# PCB_Telemetria_2020.net
KiCad netlist of a schematic drawn in EAGLE
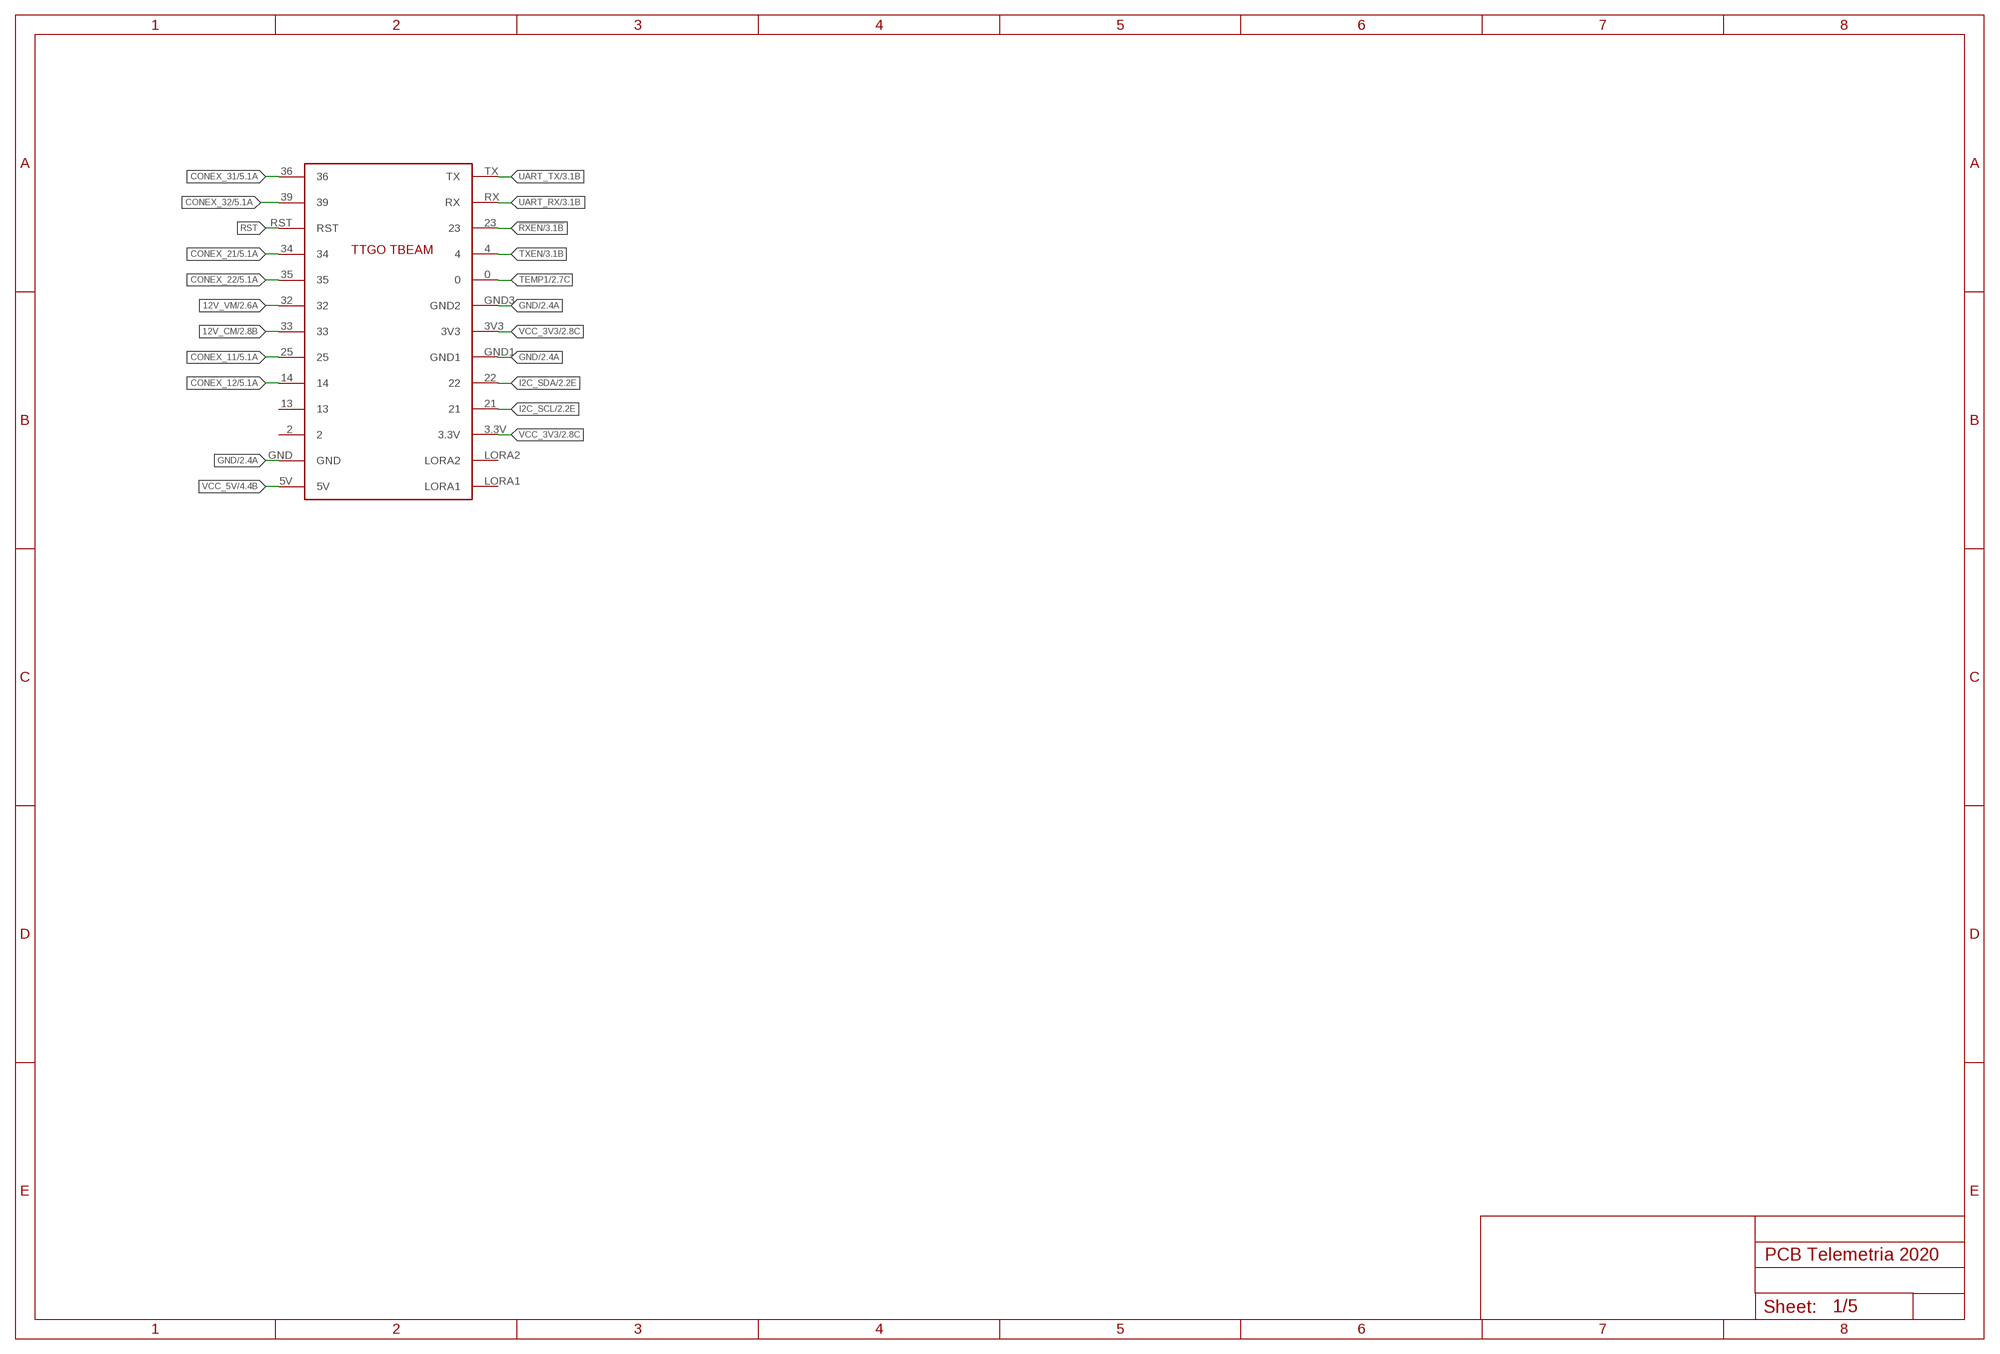
[diagram p0: schematic, sheet 1]
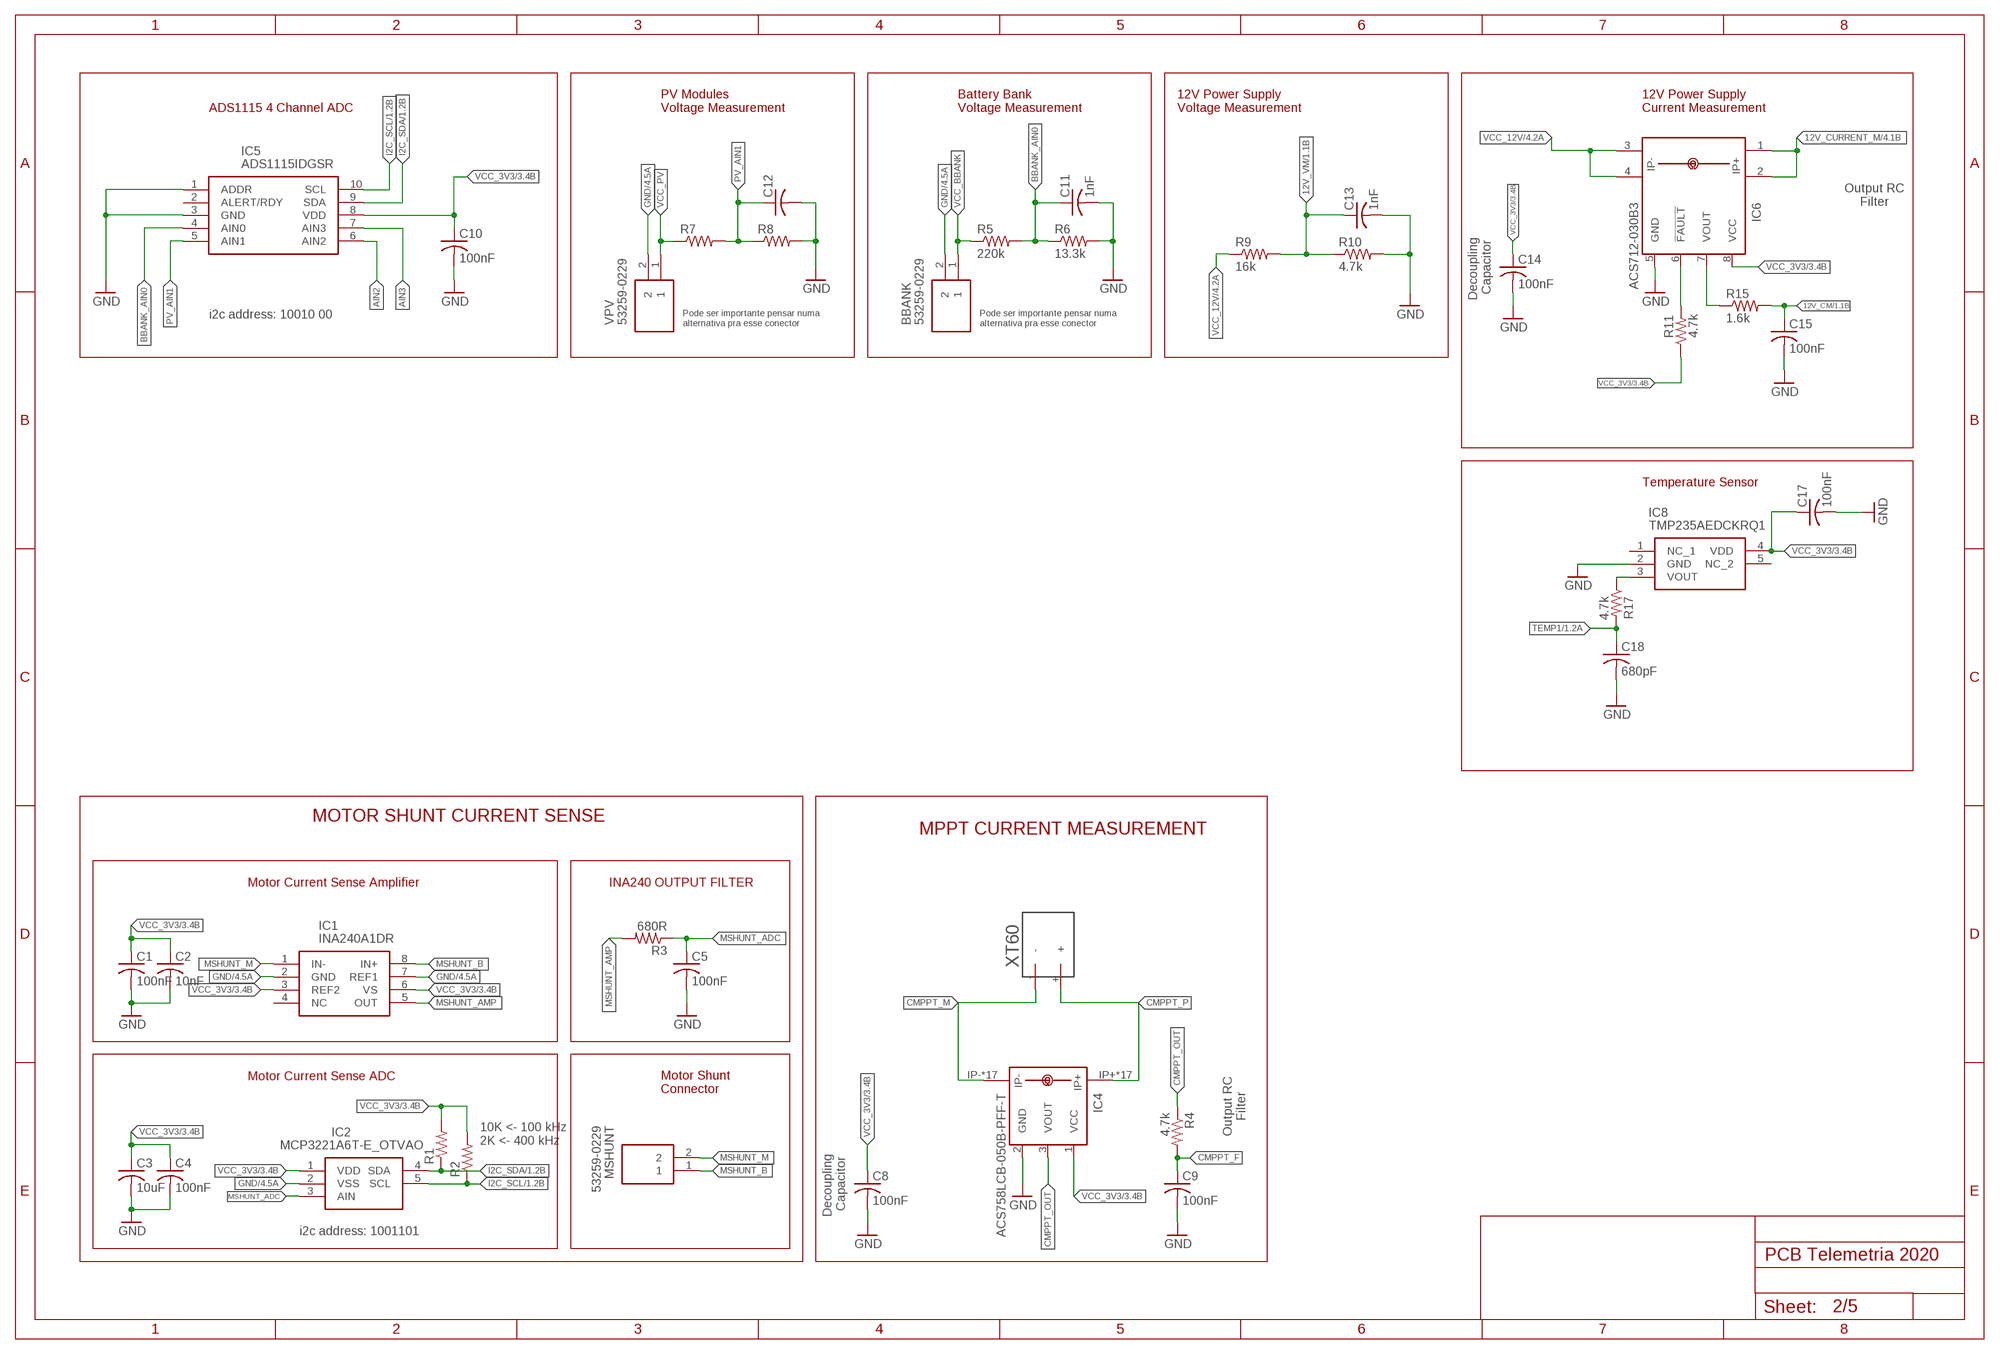
[diagram p1: schematic, sheet 2]
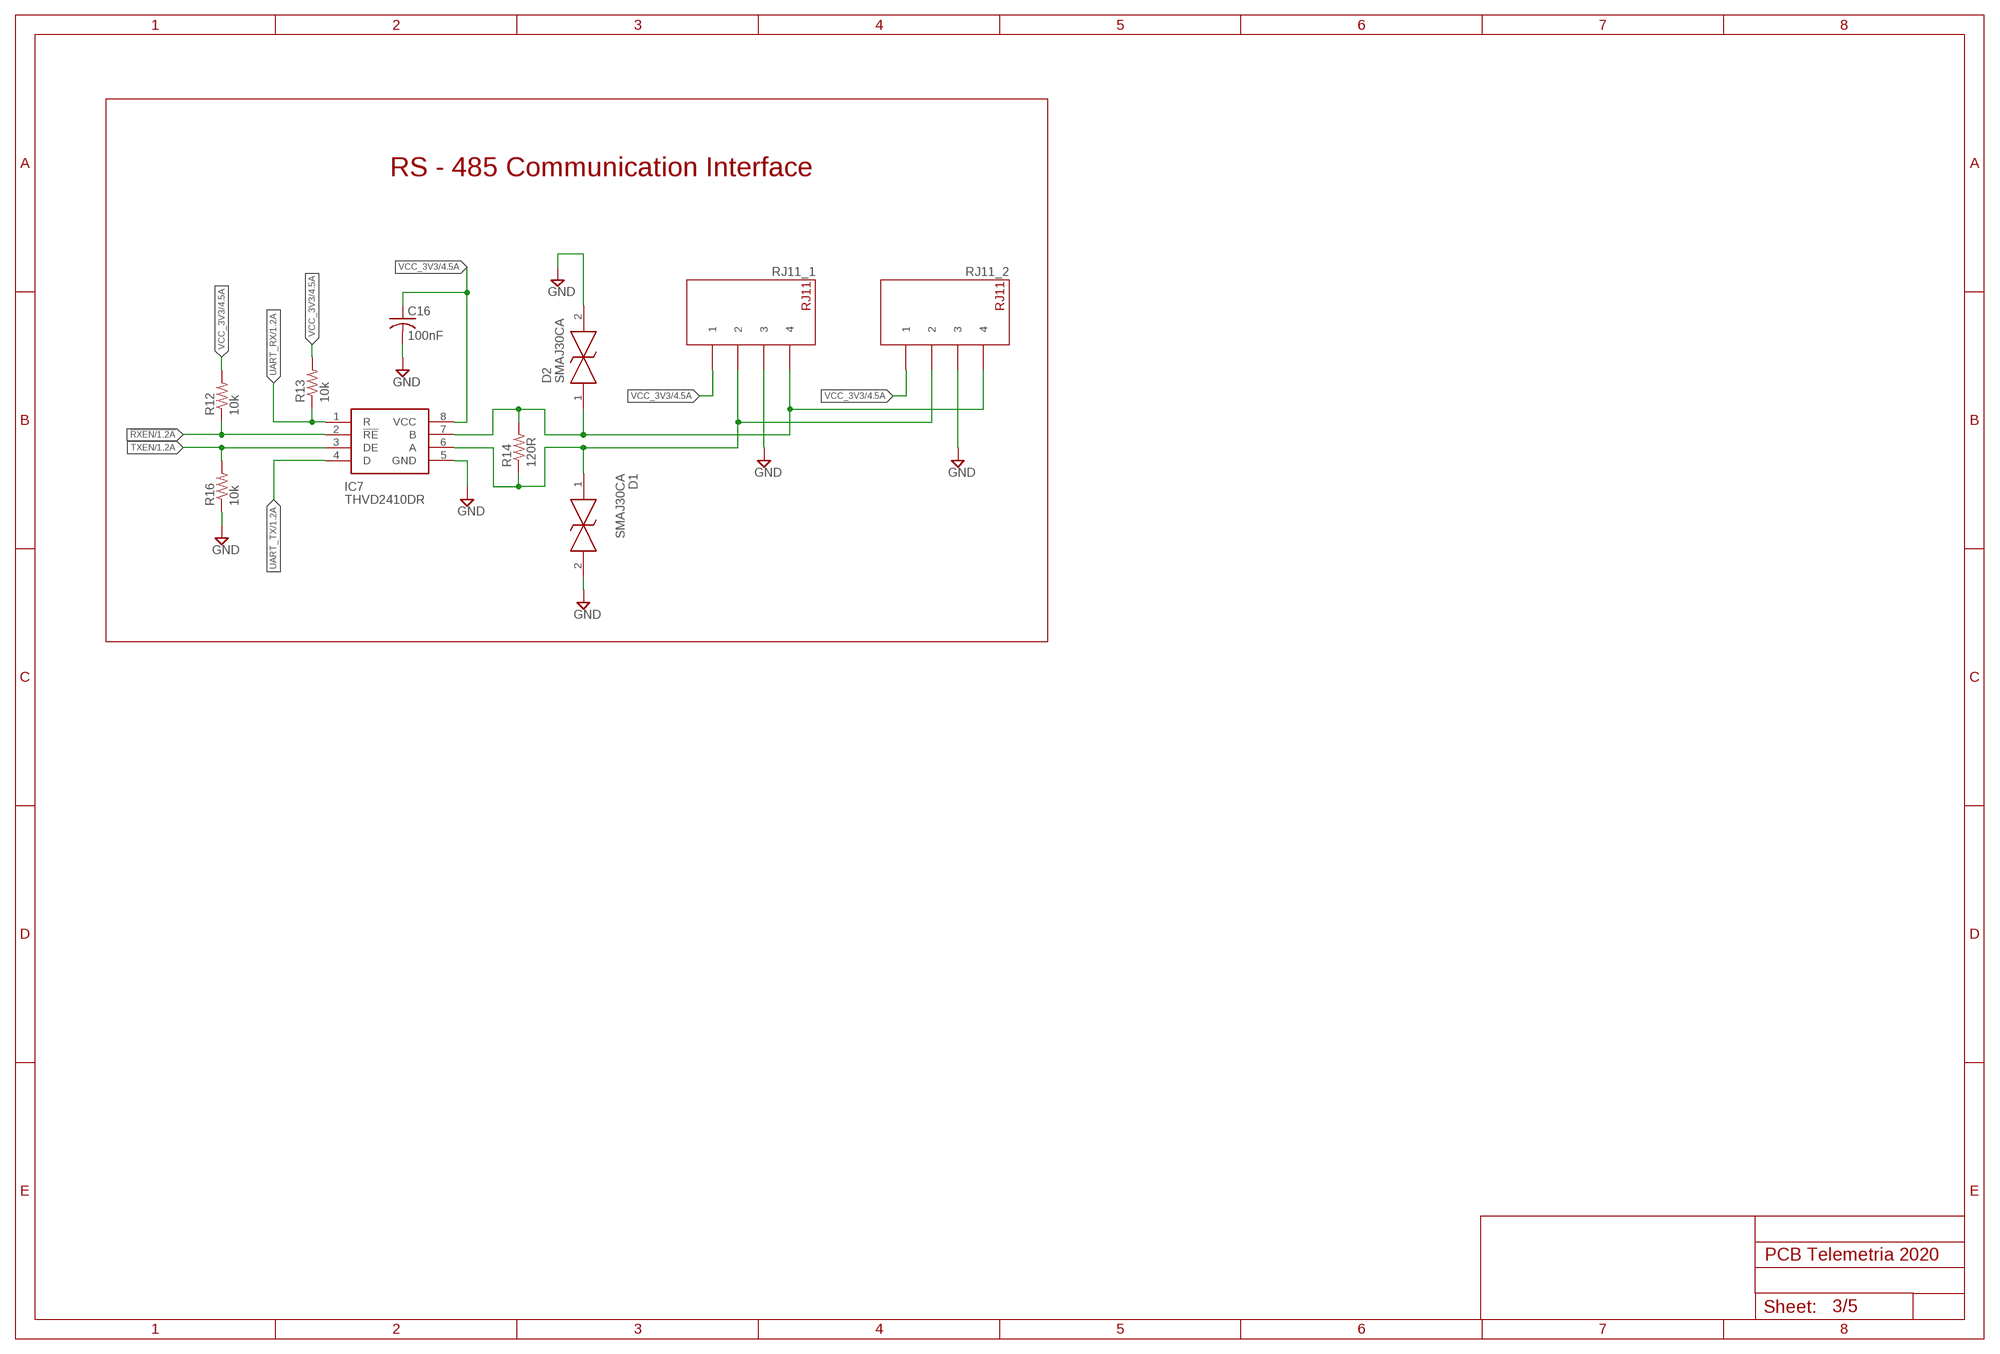
[diagram p2: schematic, sheet 3]
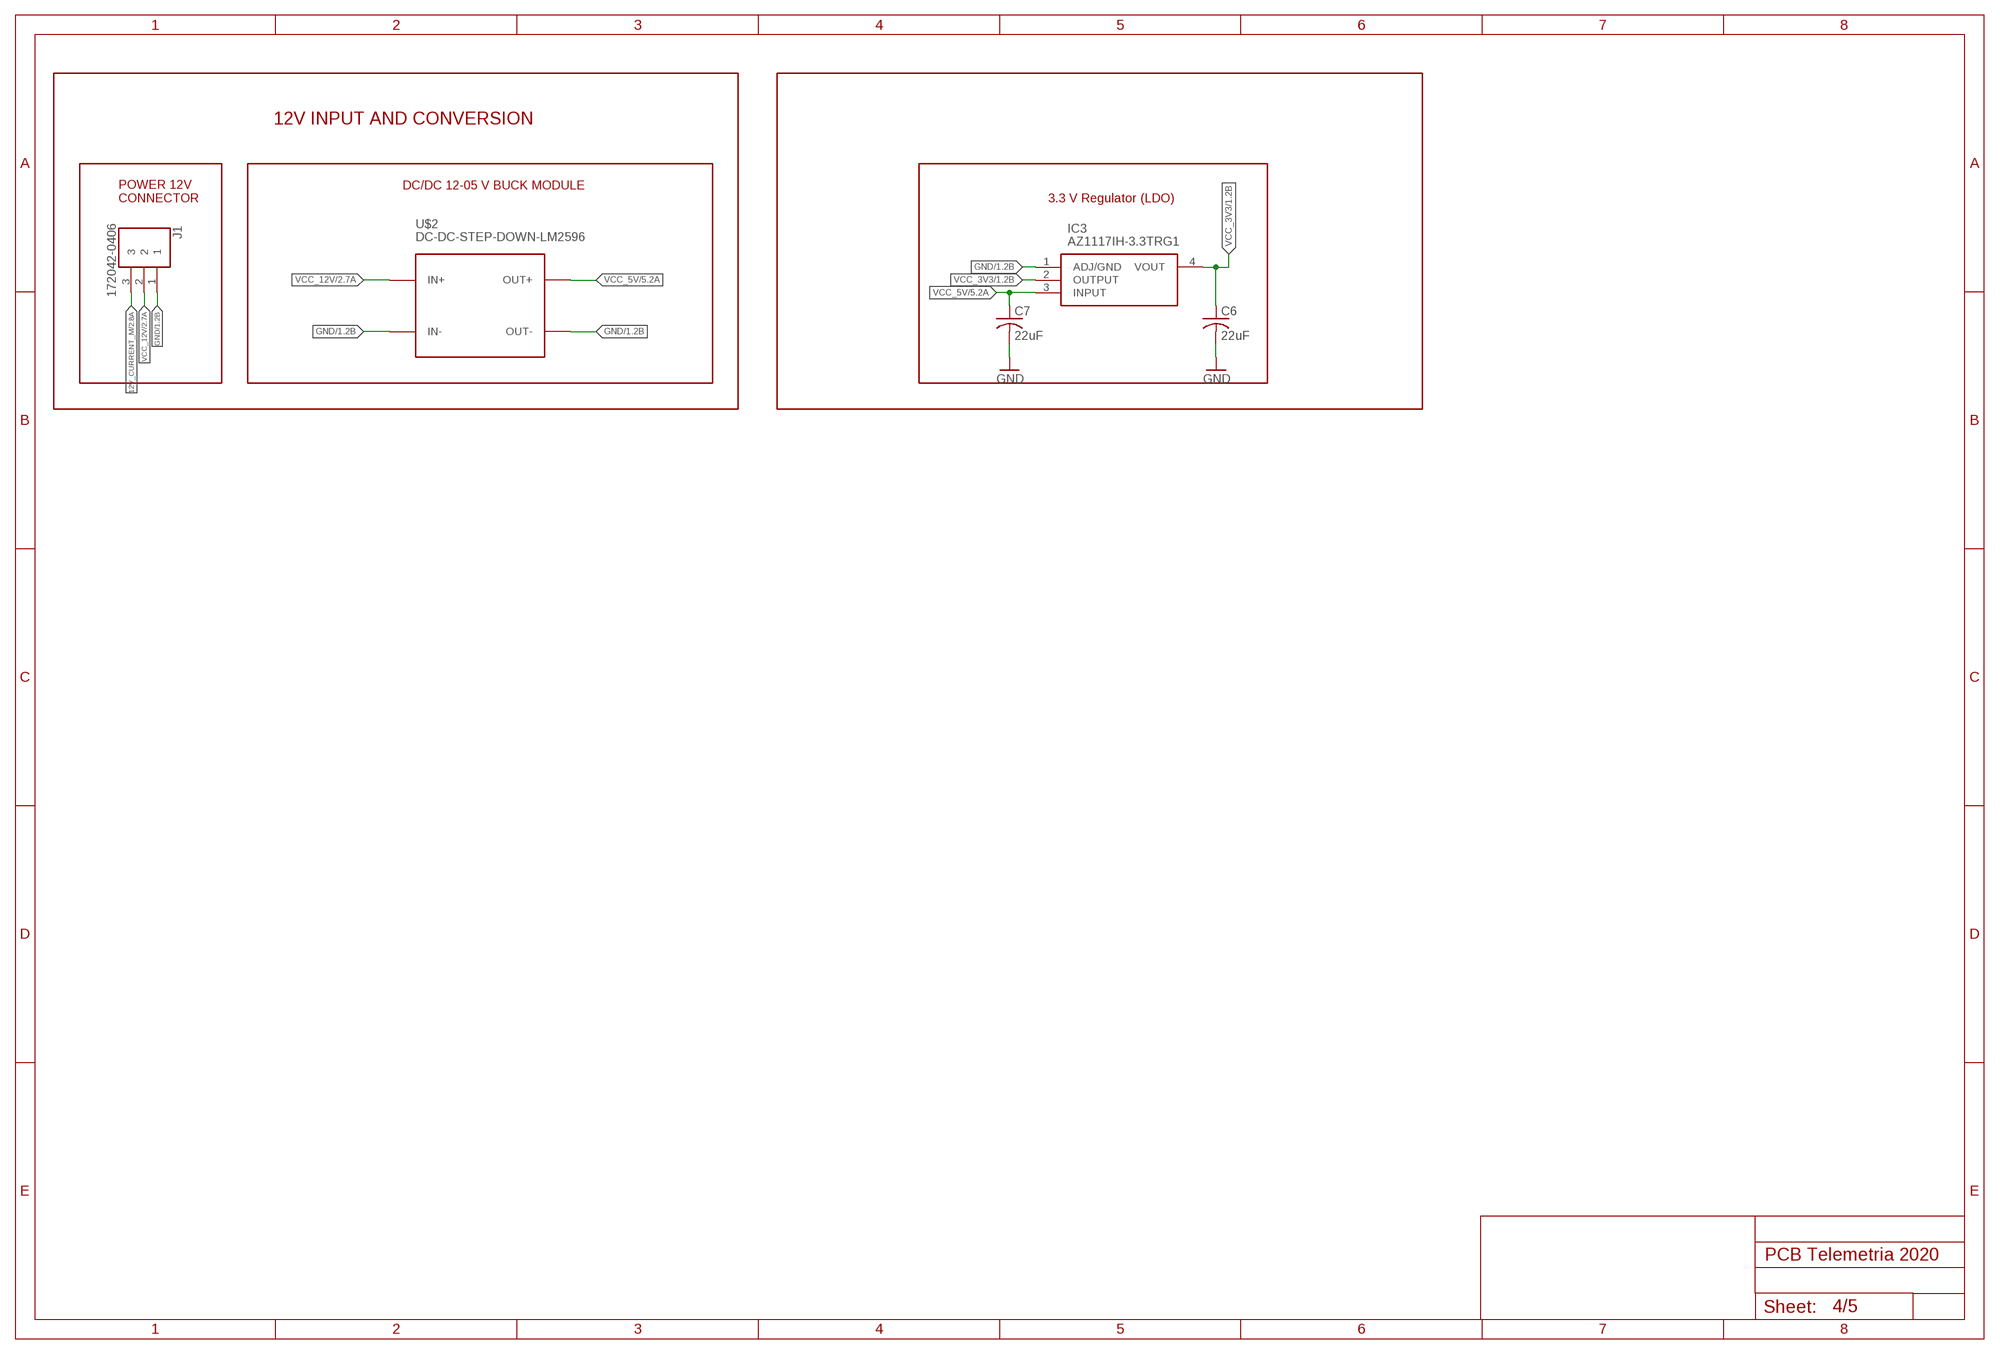
[diagram p3: schematic, sheet 4]
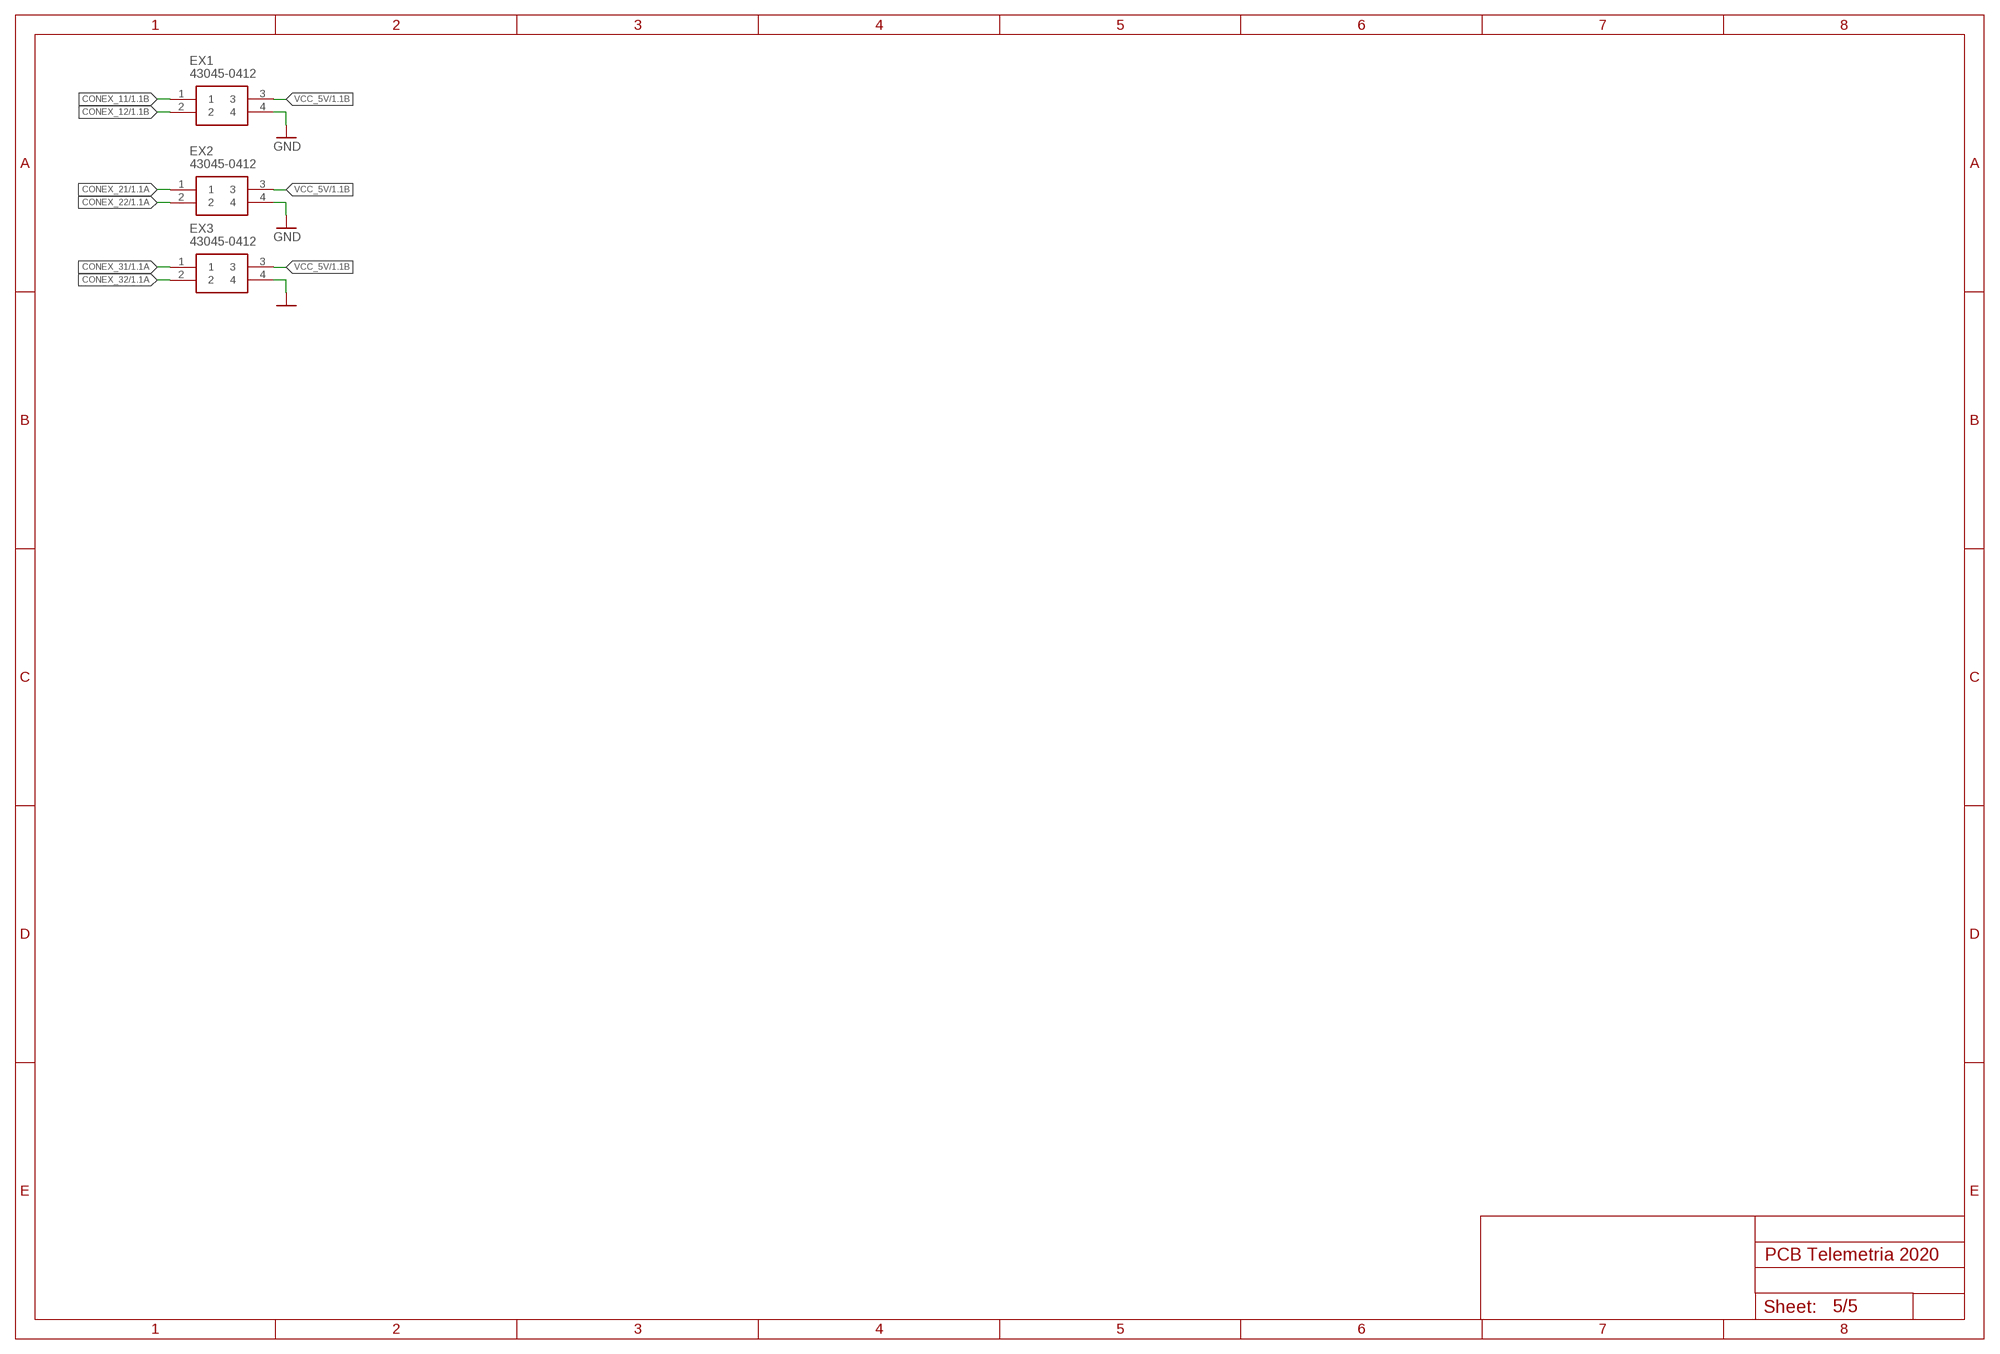
[diagram p4: schematic, sheet 5]

(export (version "E")
  (design (tool "Eeschema 10.0.6"))
  (components
    (comp (ref "U$1")
      (value "TTGOBEAM")
      (footprint "eagle-import:TTGOBEAM")
      (libsource (lib "eagle-import") (part "TTGOBEAM"))
    )
    (comp (ref "EX1")
      (value "43045-0412")
      (footprint "eagle-import:43045-0412")
      (fields (field (name "MOUSER_PART_NUMBER") "538-43045-0412"))
      (libsource (lib "eagle-import") (part "43045-0412"))
    )
    (comp (ref "EX2")
      (value "43045-0412")
      (footprint "eagle-import:43045-0412")
      (fields (field (name "MOUSER_PART_NUMBER") "538-43045-0412"))
      (libsource (lib "eagle-import") (part "43045-0412"))
    )
    (comp (ref "EX3")
      (value "43045-0412")
      (footprint "eagle-import:43045-0412")
      (fields (field (name "MOUSER_PART_NUMBER") "538-43045-0412"))
      (libsource (lib "eagle-import") (part "43045-0412"))
    )
    (comp (ref "C16")
      (value "100nF")
      (footprint "eagle-import:C0805")
      (libsource (lib "eagle-import") (part "C-USC0805"))
    )
    (comp (ref "D1")
      (value "SMAJ30CA")
      (footprint "eagle-import:DIONM5026X229N")
      (fields (field (name "MOUSER_PART_NUMBER") "576-SMAJ30CA"))
      (libsource (lib "eagle-import") (part "SMAJ30CA"))
    )
    (comp (ref "D2")
      (value "SMAJ30CA")
      (footprint "eagle-import:DIONM5026X229N")
      (fields (field (name "MOUSER_PART_NUMBER") "576-SMAJ30CA"))
      (libsource (lib "eagle-import") (part "SMAJ30CA"))
    )
    (comp (ref "IC7")
      (value "THVD2410DR")
      (footprint "eagle-import:SOIC127P600X175-8N")
      (fields (field (name "MOUSER_PART_NUMBER") "595-THVD2410DR"))
      (libsource (lib "eagle-import") (part "THVD2410DR"))
    )
    (comp (ref "R12")
      (value "10k")
      (footprint "eagle-import:M0805")
      (libsource (lib "eagle-import") (part "R-US_M0805"))
    )
    (comp (ref "R13")
      (value "10k")
      (footprint "eagle-import:M0805")
      (libsource (lib "eagle-import") (part "R-US_M0805"))
    )
    (comp (ref "R14")
      (value "120R")
      (footprint "eagle-import:M0805")
      (libsource (lib "eagle-import") (part "R-US_M0805"))
    )
    (comp (ref "R16")
      (value "10k")
      (footprint "eagle-import:M0805")
      (libsource (lib "eagle-import") (part "R-US_M0805"))
    )
    (comp (ref "RJ11_1")
      (value "TFC44")
      (footprint "eagle-import:TFC44")
      (libsource (lib "eagle-import") (part "TFC44"))
    )
    (comp (ref "RJ11_2")
      (value "TFC44")
      (footprint "eagle-import:TFC44")
      (libsource (lib "eagle-import") (part "TFC44"))
    )
    (comp (ref "C6")
      (value "22uF")
      (footprint "eagle-import:C0805")
      (libsource (lib "eagle-import") (part "C-USC0805"))
    )
    (comp (ref "C7")
      (value "22uF")
      (footprint "eagle-import:C0805")
      (libsource (lib "eagle-import") (part "C-USC0805"))
    )
    (comp (ref "IC3")
      (value "AZ1117IH-3.3TRG1")
      (footprint "eagle-import:SOT230P700X170-4N")
      (fields (field (name "MOUSER_PART_NUMBER") "621-AZ1117IH-3.3TRG1"))
      (libsource (lib "eagle-import") (part "AZ1117IH-3.3TRG1"))
    )
    (comp (ref "J1")
      (value "172042-0406")
      (footprint "eagle-import:MOLEX_172042-0406")
      (fields (field (name "MF") "Molex") (field (name "MP") "172042-0302"))
      (libsource (lib "eagle-import") (part "172042-0406"))
    )
    (comp (ref "U$2")
      (value "DC-DC-STEP-DOWN-LM2596")
      (footprint "eagle-import:DC-DC-STEP-DOWN-LM2596")
      (libsource (lib "eagle-import") (part "DC-DC-STEP-DOWN-LM2596"))
    )
    (comp (ref "BBANK")
      (value "53259-0229")
      (footprint "eagle-import:0532590229")
      (fields (field (name "MOUSER_PART_NUMBER") "538-53259-0229"))
      (libsource (lib "eagle-import") (part "53259-0229"))
    )
    (comp (ref "C1")
      (value "100nF")
      (footprint "eagle-import:C0805")
      (libsource (lib "eagle-import") (part "C-USC0805"))
    )
    (comp (ref "C2")
      (value "10nF")
      (footprint "eagle-import:C0805")
      (libsource (lib "eagle-import") (part "C-USC0805"))
    )
    (comp (ref "C3")
      (value "10uF")
      (footprint "eagle-import:C0805")
      (libsource (lib "eagle-import") (part "C-USC0805"))
    )
    (comp (ref "C4")
      (value "100nF")
      (footprint "eagle-import:C0805")
      (libsource (lib "eagle-import") (part "C-USC0805"))
    )
    (comp (ref "C5")
      (value "100nF")
      (footprint "eagle-import:C0805")
      (libsource (lib "eagle-import") (part "C-USC0805"))
    )
    (comp (ref "C8")
      (value "100nF")
      (footprint "eagle-import:C0805")
      (libsource (lib "eagle-import") (part "C-USC0805"))
    )
    (comp (ref "C9")
      (value "100nF")
      (footprint "eagle-import:C0805")
      (libsource (lib "eagle-import") (part "C-USC0805"))
    )
    (comp (ref "C10")
      (value "100nF")
      (footprint "eagle-import:C0805")
      (libsource (lib "eagle-import") (part "C-USC0805"))
    )
    (comp (ref "C11")
      (value "1nF")
      (footprint "eagle-import:C0805")
      (libsource (lib "eagle-import") (part "C-USC0805"))
    )
    (comp (ref "C12")
      (value "C-USC0805")
      (footprint "eagle-import:C0805")
      (libsource (lib "eagle-import") (part "C-USC0805"))
    )
    (comp (ref "C13")
      (value "1nF")
      (footprint "eagle-import:C0805")
      (libsource (lib "eagle-import") (part "C-USC0805"))
    )
    (comp (ref "C14")
      (value "100nF")
      (footprint "eagle-import:C0805")
      (libsource (lib "eagle-import") (part "C-USC0805"))
    )
    (comp (ref "C15")
      (value "100nF")
      (footprint "eagle-import:C0805")
      (libsource (lib "eagle-import") (part "C-USC0805"))
    )
    (comp (ref "C17")
      (value "100nF")
      (footprint "eagle-import:C0805")
      (libsource (lib "eagle-import") (part "C-USC0805"))
    )
    (comp (ref "C18")
      (value "680pF")
      (footprint "eagle-import:C0805")
      (libsource (lib "eagle-import") (part "C-USC0805"))
    )
    (comp (ref "IC1")
      (value "INA240A1DR")
      (footprint "eagle-import:SOIC127P600X175-8N")
      (fields (field (name "MOUSER_PART_NUMBER") "595-INA240A1DR"))
      (libsource (lib "eagle-import") (part "INA240A1DR"))
    )
    (comp (ref "IC2")
      (value "MCP3221A6T-E_OTVAO")
      (footprint "eagle-import:SOT95P280X145-5N")
      (fields
        (field (name "MANUFACTURER_PART_NUMBER") "MCP3221A6T-E/OTVAO")
        (field (name "MOUSER_PART_NUMBER") "579-MCP3221A6TEOTVAO")
      )
      (libsource (lib "eagle-import") (part "MCP3221A6T-E_OTVAO"))
    )
    (comp (ref "IC4")
      (value "ACS758LCB-050B-PFF-T")
      (footprint "eagle-import:CB-PFF")
      (libsource (lib "eagle-import") (part "ACS758LCB-050B-PFF-T"))
    )
    (comp (ref "IC5")
      (value "ADS1115IDGSR")
      (footprint "eagle-import:SOP50P490X110-10N")
      (fields (field (name "MOUSER_PART_NUMBER") "595-ADS1115IDGSR"))
      (libsource (lib "eagle-import") (part "ADS1115IDGSR"))
    )
    (comp (ref "IC6")
      (value "ACS712-030B3")
      (footprint "eagle-import:SOIC8")
      (libsource (lib "eagle-import") (part "ACS712-LC"))
    )
    (comp (ref "IC8")
      (value "TMP235AEDCKRQ1")
      (footprint "eagle-import:SOT65P210X110-5N")
      (fields (field (name "MOUSER_PART_NUMBER") "595-TMP235AEDCKRQ1"))
      (libsource (lib "eagle-import") (part "TMP235AEDCKRQ1"))
    )
    (comp (ref "MSHUNT")
      (value "53259-0229")
      (footprint "eagle-import:0532590229")
      (fields (field (name "MOUSER_PART_NUMBER") "538-53259-0229"))
      (libsource (lib "eagle-import") (part "53259-0229"))
    )
    (comp (ref "R1")
      (value "R-US_R0805")
      (footprint "eagle-import:R0805")
      (libsource (lib "eagle-import") (part "R-US_R0805"))
    )
    (comp (ref "R2")
      (value "R-US_R0805")
      (footprint "eagle-import:R0805")
      (libsource (lib "eagle-import") (part "R-US_R0805"))
    )
    (comp (ref "R3")
      (value "680R")
      (footprint "eagle-import:R0805")
      (libsource (lib "eagle-import") (part "R-US_R0805"))
    )
    (comp (ref "R4")
      (value "4.7k")
      (footprint "eagle-import:R0805")
      (libsource (lib "eagle-import") (part "R-US_R0805"))
    )
    (comp (ref "R5")
      (value "220k")
      (footprint "eagle-import:R0805")
      (libsource (lib "eagle-import") (part "R-US_R0805"))
    )
    (comp (ref "R6")
      (value "13.3k")
      (footprint "eagle-import:R0805")
      (libsource (lib "eagle-import") (part "R-US_R0805"))
    )
    (comp (ref "R7")
      (value "R-US_R0805")
      (footprint "eagle-import:R0805")
      (libsource (lib "eagle-import") (part "R-US_R0805"))
    )
    (comp (ref "R8")
      (value "R-US_R0805")
      (footprint "eagle-import:R0805")
      (libsource (lib "eagle-import") (part "R-US_R0805"))
    )
    (comp (ref "R9")
      (value "16k")
      (footprint "eagle-import:R0805")
      (libsource (lib "eagle-import") (part "R-US_R0805"))
    )
    (comp (ref "R10")
      (value "4.7k")
      (footprint "eagle-import:R0805")
      (libsource (lib "eagle-import") (part "R-US_R0805"))
    )
    (comp (ref "R11")
      (value "4.7k")
      (footprint "eagle-import:R0805")
      (libsource (lib "eagle-import") (part "R-US_R0805"))
    )
    (comp (ref "R15")
      (value "1.6k")
      (footprint "eagle-import:R0805")
      (libsource (lib "eagle-import") (part "R-US_R0805"))
    )
    (comp (ref "R17")
      (value "4.7k")
      (footprint "eagle-import:R0805")
      (libsource (lib "eagle-import") (part "R-US_R0805"))
    )
    (comp (ref "U$3")
      (value "XT60")
      (footprint "eagle-import:XT60")
      (libsource (lib "eagle-import") (part "XT60"))
    )
    (comp (ref "VPV")
      (value "53259-0229")
      (footprint "eagle-import:0532590229")
      (fields (field (name "MOUSER_PART_NUMBER") "538-53259-0229"))
      (libsource (lib "eagle-import") (part "53259-0229"))
    )
  )
  (nets
    (net (code "1") (name "12V_CM") (class "Default")
      (node (ref "C15") (pin "1") (pinfunction "1_1") (pintype "passive"))
      (node (ref "R15") (pin "2") (pinfunction "2_2") (pintype "passive"))
      (node (ref "U$1") (pin "33") (pinfunction "33_33") (pintype "bidirectional"))
    )
    (net (code "2") (name "12V_CURRENT_M") (class "Default")
      (node (ref "IC6") (pin "1") (pinfunction "IP+_1") (pintype "passive"))
      (node (ref "IC6") (pin "2") (pinfunction "IP+1_2") (pintype "passive"))
      (node (ref "J1") (pin "3") (pinfunction "3_3") (pintype "passive"))
    )
    (net (code "3") (name "12V_VM") (class "Default")
      (node (ref "C13") (pin "1") (pinfunction "1_1") (pintype "passive"))
      (node (ref "R10") (pin "1") (pinfunction "1_1") (pintype "passive"))
      (node (ref "R9") (pin "2") (pinfunction "2_2") (pintype "passive"))
      (node (ref "U$1") (pin "32") (pinfunction "32_32") (pintype "bidirectional"))
    )
    (net (code "4") (name "AIN2") (class "Default")
      (node (ref "IC5") (pin "6") (pinfunction "AIN2_6") (pintype "bidirectional"))
    )
    (net (code "5") (name "AIN3") (class "Default")
      (node (ref "IC5") (pin "7") (pinfunction "AIN3_7") (pintype "bidirectional"))
    )
    (net (code "6") (name "BBANK_AIN0") (class "Default")
      (node (ref "C11") (pin "1") (pinfunction "1_1") (pintype "passive"))
      (node (ref "IC5") (pin "4") (pinfunction "AIN0_4") (pintype "bidirectional"))
      (node (ref "R5") (pin "2") (pinfunction "2_2") (pintype "passive"))
      (node (ref "R6") (pin "1") (pinfunction "1_1") (pintype "passive"))
    )
    (net (code "7") (name "CMPPT_F") (class "Default")
      (node (ref "C9") (pin "1") (pinfunction "1_1") (pintype "passive"))
      (node (ref "R4") (pin "2") (pinfunction "2_2") (pintype "passive"))
    )
    (net (code "8") (name "CMPPT_M") (class "Default")
      (node (ref "IC4") (pin "IP-") (pinfunction "IP-_IP-") (pintype "passive"))
      (node (ref "IC4") (pin "IP-@10") (pinfunction "IP-_IP-@10") (pintype "passive"))
      (node (ref "IC4") (pin "IP-@11") (pinfunction "IP-_IP-@11") (pintype "passive"))
      (node (ref "IC4") (pin "IP-@12") (pinfunction "IP-_IP-@12") (pintype "passive"))
      (node (ref "IC4") (pin "IP-@13") (pinfunction "IP-_IP-@13") (pintype "passive"))
      (node (ref "IC4") (pin "IP-@14") (pinfunction "IP-_IP-@14") (pintype "passive"))
      (node (ref "IC4") (pin "IP-@15") (pinfunction "IP-_IP-@15") (pintype "passive"))
      (node (ref "IC4") (pin "IP-@16") (pinfunction "IP-_IP-@16") (pintype "passive"))
      (node (ref "IC4") (pin "IP-@17") (pinfunction "IP-_IP-@17") (pintype "passive"))
      (node (ref "IC4") (pin "IP-@2") (pinfunction "IP-_IP-@2") (pintype "passive"))
      (node (ref "IC4") (pin "IP-@3") (pinfunction "IP-_IP-@3") (pintype "passive"))
      (node (ref "IC4") (pin "IP-@4") (pinfunction "IP-_IP-@4") (pintype "passive"))
      (node (ref "IC4") (pin "IP-@5") (pinfunction "IP-_IP-@5") (pintype "passive"))
      (node (ref "IC4") (pin "IP-@6") (pinfunction "IP-_IP-@6") (pintype "passive"))
      (node (ref "IC4") (pin "IP-@7") (pinfunction "IP-_IP-@7") (pintype "passive"))
      (node (ref "IC4") (pin "IP-@8") (pinfunction "IP-_IP-@8") (pintype "passive"))
      (node (ref "IC4") (pin "IP-@9") (pinfunction "IP-_IP-@9") (pintype "passive"))
      (node (ref "U$3") (pin "-") (pinfunction "-_-") (pintype "bidirectional"))
    )
    (net (code "9") (name "CMPPT_OUT") (class "Default")
      (node (ref "IC4") (pin "3") (pinfunction "VOUT_3") (pintype "output"))
      (node (ref "R4") (pin "1") (pinfunction "1_1") (pintype "passive"))
    )
    (net (code "10") (name "CMPPT_P") (class "Default")
      (node (ref "IC4") (pin "IP+") (pinfunction "IP+_IP+") (pintype "passive"))
      (node (ref "IC4") (pin "IP+@10") (pinfunction "IP+_IP+@10") (pintype "passive"))
      (node (ref "IC4") (pin "IP+@11") (pinfunction "IP+_IP+@11") (pintype "passive"))
      (node (ref "IC4") (pin "IP+@12") (pinfunction "IP+_IP+@12") (pintype "passive"))
      (node (ref "IC4") (pin "IP+@13") (pinfunction "IP+_IP+@13") (pintype "passive"))
      (node (ref "IC4") (pin "IP+@14") (pinfunction "IP+_IP+@14") (pintype "passive"))
      (node (ref "IC4") (pin "IP+@15") (pinfunction "IP+_IP+@15") (pintype "passive"))
      (node (ref "IC4") (pin "IP+@16") (pinfunction "IP+_IP+@16") (pintype "passive"))
      (node (ref "IC4") (pin "IP+@17") (pinfunction "IP+_IP+@17") (pintype "passive"))
      (node (ref "IC4") (pin "IP+@2") (pinfunction "IP+_IP+@2") (pintype "passive"))
      (node (ref "IC4") (pin "IP+@3") (pinfunction "IP+_IP+@3") (pintype "passive"))
      (node (ref "IC4") (pin "IP+@4") (pinfunction "IP+_IP+@4") (pintype "passive"))
      (node (ref "IC4") (pin "IP+@5") (pinfunction "IP+_IP+@5") (pintype "passive"))
      (node (ref "IC4") (pin "IP+@6") (pinfunction "IP+_IP+@6") (pintype "passive"))
      (node (ref "IC4") (pin "IP+@7") (pinfunction "IP+_IP+@7") (pintype "passive"))
      (node (ref "IC4") (pin "IP+@8") (pinfunction "IP+_IP+@8") (pintype "passive"))
      (node (ref "IC4") (pin "IP+@9") (pinfunction "IP+_IP+@9") (pintype "passive"))
      (node (ref "U$3") (pin "+") (pinfunction "+_+") (pintype "bidirectional"))
    )
    (net (code "11") (name "CONEX_11") (class "Default")
      (node (ref "EX1") (pin "1") (pinfunction "1_1") (pintype "bidirectional"))
      (node (ref "U$1") (pin "25") (pinfunction "25_25") (pintype "bidirectional"))
    )
    (net (code "12") (name "CONEX_12") (class "Default")
      (node (ref "EX1") (pin "2") (pinfunction "2_2") (pintype "bidirectional"))
      (node (ref "U$1") (pin "14") (pinfunction "14_14") (pintype "bidirectional"))
    )
    (net (code "13") (name "CONEX_21") (class "Default")
      (node (ref "EX2") (pin "1") (pinfunction "1_1") (pintype "bidirectional"))
      (node (ref "U$1") (pin "34") (pinfunction "34_34") (pintype "bidirectional"))
    )
    (net (code "14") (name "CONEX_22") (class "Default")
      (node (ref "EX2") (pin "2") (pinfunction "2_2") (pintype "bidirectional"))
      (node (ref "U$1") (pin "35") (pinfunction "35_35") (pintype "bidirectional"))
    )
    (net (code "15") (name "CONEX_31") (class "Default")
      (node (ref "EX3") (pin "1") (pinfunction "1_1") (pintype "bidirectional"))
      (node (ref "U$1") (pin "36") (pinfunction "36_36") (pintype "bidirectional"))
    )
    (net (code "16") (name "CONEX_32") (class "Default")
      (node (ref "EX3") (pin "2") (pinfunction "2_2") (pintype "bidirectional"))
      (node (ref "U$1") (pin "39") (pinfunction "39_39") (pintype "bidirectional"))
    )
    (net (code "17") (name "GND") (class "Default")
      (node (ref "BBANK") (pin "2") (pinfunction "2_2") (pintype "bidirectional"))
      (node (ref "C1") (pin "2") (pinfunction "2_2") (pintype "passive"))
      (node (ref "C10") (pin "2") (pinfunction "2_2") (pintype "passive"))
      (node (ref "C11") (pin "2") (pinfunction "2_2") (pintype "passive"))
      (node (ref "C12") (pin "2") (pinfunction "2_2") (pintype "passive"))
      (node (ref "C13") (pin "2") (pinfunction "2_2") (pintype "passive"))
      (node (ref "C14") (pin "2") (pinfunction "2_2") (pintype "passive"))
      (node (ref "C15") (pin "2") (pinfunction "2_2") (pintype "passive"))
      (node (ref "C16") (pin "2") (pinfunction "2_2") (pintype "passive"))
      (node (ref "C17") (pin "2") (pinfunction "2_2") (pintype "passive"))
      (node (ref "C18") (pin "2") (pinfunction "2_2") (pintype "passive"))
      (node (ref "C2") (pin "2") (pinfunction "2_2") (pintype "passive"))
      (node (ref "C3") (pin "2") (pinfunction "2_2") (pintype "passive"))
      (node (ref "C4") (pin "2") (pinfunction "2_2") (pintype "passive"))
      (node (ref "C5") (pin "2") (pinfunction "2_2") (pintype "passive"))
      (node (ref "C6") (pin "2") (pinfunction "2_2") (pintype "passive"))
      (node (ref "C7") (pin "2") (pinfunction "2_2") (pintype "passive"))
      (node (ref "C8") (pin "2") (pinfunction "2_2") (pintype "passive"))
      (node (ref "C9") (pin "2") (pinfunction "2_2") (pintype "passive"))
      (node (ref "D1") (pin "2") (pinfunction "2_2") (pintype "bidirectional"))
      (node (ref "D2") (pin "2") (pinfunction "2_2") (pintype "bidirectional"))
      (node (ref "EX1") (pin "4") (pinfunction "4_4") (pintype "bidirectional"))
      (node (ref "EX2") (pin "4") (pinfunction "4_4") (pintype "bidirectional"))
      (node (ref "EX3") (pin "4") (pinfunction "4_4") (pintype "bidirectional"))
      (node (ref "IC1") (pin "2") (pinfunction "GND_2") (pintype "bidirectional"))
      (node (ref "IC1") (pin "7") (pinfunction "REF1_7") (pintype "bidirectional"))
      (node (ref "IC2") (pin "2") (pinfunction "VSS_2") (pintype "bidirectional"))
      (node (ref "IC3") (pin "1") (pinfunction "ADJ/GND_1") (pintype "bidirectional"))
      (node (ref "IC4") (pin "2") (pinfunction "GND_2") (pintype "power_in"))
      (node (ref "IC5") (pin "1") (pinfunction "ADDR_1") (pintype "bidirectional"))
      (node (ref "IC5") (pin "3") (pinfunction "GND_3") (pintype "bidirectional"))
      (node (ref "IC6") (pin "5") (pinfunction "GND_5") (pintype "power_in"))
      (node (ref "IC7") (pin "5") (pinfunction "GND_5") (pintype "bidirectional"))
      (node (ref "IC8") (pin "2") (pinfunction "GND_2") (pintype "bidirectional"))
      (node (ref "J1") (pin "1") (pinfunction "1_1") (pintype "passive"))
      (node (ref "R10") (pin "2") (pinfunction "2_2") (pintype "passive"))
      (node (ref "R16") (pin "1") (pinfunction "1_1") (pintype "passive"))
      (node (ref "R6") (pin "2") (pinfunction "2_2") (pintype "passive"))
      (node (ref "R8") (pin "2") (pinfunction "2_2") (pintype "passive"))
      (node (ref "RJ11_1") (pin "P$3") (pinfunction "3_P$3") (pintype "bidirectional"))
      (node (ref "RJ11_2") (pin "P$3") (pinfunction "3_P$3") (pintype "bidirectional"))
      (node (ref "U$1") (pin "GND") (pinfunction "GND_GND") (pintype "bidirectional"))
      (node (ref "U$1") (pin "GND1") (pinfunction "GND1_GND1") (pintype "bidirectional"))
      (node (ref "U$1") (pin "GND3") (pinfunction "GND2_GND3") (pintype "bidirectional"))
      (node (ref "U$2") (pin "IN-") (pinfunction "IN-_IN-") (pintype "bidirectional"))
      (node (ref "U$2") (pin "OUT-") (pinfunction "OUT-_OUT-") (pintype "bidirectional"))
      (node (ref "VPV") (pin "2") (pinfunction "2_2") (pintype "bidirectional"))
    )
    (net (code "18") (name "I2C_SCL") (class "Default")
      (node (ref "IC2") (pin "5") (pinfunction "SCL_5") (pintype "bidirectional"))
      (node (ref "IC5") (pin "10") (pinfunction "SCL_10") (pintype "bidirectional"))
      (node (ref "R2") (pin "1") (pinfunction "1_1") (pintype "passive"))
      (node (ref "U$1") (pin "21") (pinfunction "21_21") (pintype "bidirectional"))
    )
    (net (code "19") (name "I2C_SDA") (class "Default")
      (node (ref "IC2") (pin "4") (pinfunction "SDA_4") (pintype "bidirectional"))
      (node (ref "IC5") (pin "9") (pinfunction "SDA_9") (pintype "bidirectional"))
      (node (ref "R1") (pin "1") (pinfunction "1_1") (pintype "passive"))
      (node (ref "U$1") (pin "22") (pinfunction "22_22") (pintype "bidirectional"))
    )
    (net (code "20") (name "MSHUNT_ADC") (class "Default")
      (node (ref "C5") (pin "1") (pinfunction "1_1") (pintype "passive"))
      (node (ref "IC2") (pin "3") (pinfunction "AIN_3") (pintype "bidirectional"))
      (node (ref "R3") (pin "1") (pinfunction "1_1") (pintype "passive"))
    )
    (net (code "21") (name "MSHUNT_AMP") (class "Default")
      (node (ref "IC1") (pin "5") (pinfunction "OUT_5") (pintype "bidirectional"))
      (node (ref "R3") (pin "2") (pinfunction "2_2") (pintype "passive"))
    )
    (net (code "22") (name "MSHUNT_B") (class "Default")
      (node (ref "IC1") (pin "8") (pinfunction "IN+_8") (pintype "bidirectional"))
      (node (ref "MSHUNT") (pin "1") (pinfunction "1_1") (pintype "bidirectional"))
    )
    (net (code "23") (name "MSHUNT_M") (class "Default")
      (node (ref "IC1") (pin "1") (pinfunction "IN-_1") (pintype "bidirectional"))
      (node (ref "MSHUNT") (pin "2") (pinfunction "2_2") (pintype "bidirectional"))
    )
    (net (code "24") (name "Net-(IC6-VOUT)") (class "Default")
      (node (ref "IC6") (pin "7") (pinfunction "VOUT_7") (pintype "output"))
      (node (ref "R15") (pin "1") (pinfunction "1_1") (pintype "passive"))
    )
    (net (code "25") (name "Net-(IC6-~{FAULT})") (class "Default")
      (node (ref "IC6") (pin "6") (pinfunction "~{FAULT}_6") (pintype "bidirectional"))
      (node (ref "R11") (pin "2") (pinfunction "2_2") (pintype "passive"))
    )
    (net (code "26") (name "Net-(IC7-A)") (class "Default")
      (node (ref "D1") (pin "1") (pinfunction "1_1") (pintype "bidirectional"))
      (node (ref "IC7") (pin "6") (pinfunction "A_6") (pintype "bidirectional"))
      (node (ref "R14") (pin "1") (pinfunction "1_1") (pintype "passive"))
      (node (ref "RJ11_1") (pin "P$2") (pinfunction "2_P$2") (pintype "bidirectional"))
      (node (ref "RJ11_2") (pin "P$2") (pinfunction "2_P$2") (pintype "bidirectional"))
    )
    (net (code "27") (name "Net-(IC7-B)") (class "Default")
      (node (ref "D2") (pin "1") (pinfunction "1_1") (pintype "bidirectional"))
      (node (ref "IC7") (pin "7") (pinfunction "B_7") (pintype "bidirectional"))
      (node (ref "R14") (pin "2") (pinfunction "2_2") (pintype "passive"))
      (node (ref "RJ11_1") (pin "P$4") (pinfunction "4_P$4") (pintype "bidirectional"))
      (node (ref "RJ11_2") (pin "P$4") (pinfunction "4_P$4") (pintype "bidirectional"))
    )
    (net (code "28") (name "Net-(IC8-VOUT)") (class "Default")
      (node (ref "IC8") (pin "3") (pinfunction "VOUT_3") (pintype "bidirectional"))
      (node (ref "R17") (pin "1") (pinfunction "1_1") (pintype "passive"))
    )
    (net (code "29") (name "PV_AIN1") (class "Default")
      (node (ref "C12") (pin "1") (pinfunction "1_1") (pintype "passive"))
      (node (ref "IC5") (pin "5") (pinfunction "AIN1_5") (pintype "bidirectional"))
      (node (ref "R7") (pin "2") (pinfunction "2_2") (pintype "passive"))
      (node (ref "R8") (pin "1") (pinfunction "1_1") (pintype "passive"))
    )
    (net (code "30") (name "RST") (class "Default")
      (node (ref "U$1") (pin "RST") (pinfunction "RST_RST") (pintype "bidirectional"))
    )
    (net (code "31") (name "TEMP1") (class "Default")
      (node (ref "C18") (pin "1") (pinfunction "1_1") (pintype "passive"))
      (node (ref "R17") (pin "2") (pinfunction "2_2") (pintype "passive"))
      (node (ref "U$1") (pin "0") (pinfunction "0_0") (pintype "bidirectional"))
    )
    (net (code "32") (name "TXEN") (class "Default")
      (node (ref "IC7") (pin "3") (pinfunction "DE_3") (pintype "bidirectional"))
      (node (ref "R16") (pin "2") (pinfunction "2_2") (pintype "passive"))
      (node (ref "U$1") (pin "4") (pinfunction "4_4") (pintype "bidirectional"))
    )
    (net (code "33") (name "UART_RX") (class "Default")
      (node (ref "IC7") (pin "1") (pinfunction "R_1") (pintype "bidirectional"))
      (node (ref "R13") (pin "1") (pinfunction "1_1") (pintype "passive"))
      (node (ref "U$1") (pin "RX") (pinfunction "RX_RX") (pintype "bidirectional"))
    )
    (net (code "34") (name "UART_TX") (class "Default")
      (node (ref "IC7") (pin "4") (pinfunction "D_4") (pintype "bidirectional"))
      (node (ref "U$1") (pin "TX") (pinfunction "TX_TX") (pintype "bidirectional"))
    )
    (net (code "35") (name "VCC_3V3") (class "Default")
      (node (ref "C1") (pin "1") (pinfunction "1_1") (pintype "passive"))
      (node (ref "C10") (pin "1") (pinfunction "1_1") (pintype "passive"))
      (node (ref "C14") (pin "1") (pinfunction "1_1") (pintype "passive"))
      (node (ref "C16") (pin "1") (pinfunction "1_1") (pintype "passive"))
      (node (ref "C17") (pin "1") (pinfunction "1_1") (pintype "passive"))
      (node (ref "C2") (pin "1") (pinfunction "1_1") (pintype "passive"))
      (node (ref "C3") (pin "1") (pinfunction "1_1") (pintype "passive"))
      (node (ref "C4") (pin "1") (pinfunction "1_1") (pintype "passive"))
      (node (ref "C6") (pin "1") (pinfunction "1_1") (pintype "passive"))
      (node (ref "C8") (pin "1") (pinfunction "1_1") (pintype "passive"))
      (node (ref "IC1") (pin "3") (pinfunction "REF2_3") (pintype "bidirectional"))
      (node (ref "IC1") (pin "6") (pinfunction "VS_6") (pintype "bidirectional"))
      (node (ref "IC2") (pin "1") (pinfunction "VDD_1") (pintype "bidirectional"))
      (node (ref "IC3") (pin "2") (pinfunction "OUTPUT_2") (pintype "bidirectional"))
      (node (ref "IC3") (pin "4") (pinfunction "VOUT_4") (pintype "bidirectional"))
      (node (ref "IC4") (pin "1") (pinfunction "VCC_1") (pintype "power_in"))
      (node (ref "IC5") (pin "8") (pinfunction "VDD_8") (pintype "bidirectional"))
      (node (ref "IC6") (pin "8") (pinfunction "VCC_8") (pintype "power_in"))
      (node (ref "IC7") (pin "8") (pinfunction "VCC_8") (pintype "bidirectional"))
      (node (ref "IC8") (pin "4") (pinfunction "VDD_4") (pintype "bidirectional"))
      (node (ref "R1") (pin "2") (pinfunction "2_2") (pintype "passive"))
      (node (ref "R11") (pin "1") (pinfunction "1_1") (pintype "passive"))
      (node (ref "R12") (pin "2") (pinfunction "2_2") (pintype "passive"))
      (node (ref "R13") (pin "2") (pinfunction "2_2") (pintype "passive"))
      (node (ref "R2") (pin "2") (pinfunction "2_2") (pintype "passive"))
      (node (ref "RJ11_1") (pin "P$1") (pinfunction "1_P$1") (pintype "bidirectional"))
      (node (ref "RJ11_2") (pin "P$1") (pinfunction "1_P$1") (pintype "bidirectional"))
      (node (ref "U$1") (pin "3.3V") (pinfunction "3.3V_3.3V") (pintype "bidirectional"))
      (node (ref "U$1") (pin "3V3") (pinfunction "3V3_3V3") (pintype "bidirectional"))
    )
    (net (code "36") (name "VCC_5V") (class "Default")
      (node (ref "C7") (pin "1") (pinfunction "1_1") (pintype "passive"))
      (node (ref "EX1") (pin "3") (pinfunction "3_3") (pintype "bidirectional"))
      (node (ref "EX2") (pin "3") (pinfunction "3_3") (pintype "bidirectional"))
      (node (ref "EX3") (pin "3") (pinfunction "3_3") (pintype "bidirectional"))
      (node (ref "IC3") (pin "3") (pinfunction "INPUT_3") (pintype "bidirectional"))
      (node (ref "U$1") (pin "5V") (pinfunction "5V_5V") (pintype "bidirectional"))
      (node (ref "U$2") (pin "OUT+") (pinfunction "OUT+_OUT+") (pintype "bidirectional"))
    )
    (net (code "37") (name "VCC_12V") (class "Default")
      (node (ref "IC6") (pin "3") (pinfunction "IP-_3") (pintype "passive"))
      (node (ref "IC6") (pin "4") (pinfunction "IP-1_4") (pintype "passive"))
      (node (ref "J1") (pin "2") (pinfunction "2_2") (pintype "passive"))
      (node (ref "R9") (pin "1") (pinfunction "1_1") (pintype "passive"))
      (node (ref "U$2") (pin "IN+") (pinfunction "IN+_IN+") (pintype "bidirectional"))
    )
    (net (code "38") (name "VCC_BBANK") (class "Default")
      (node (ref "BBANK") (pin "1") (pinfunction "1_1") (pintype "bidirectional"))
      (node (ref "R5") (pin "1") (pinfunction "1_1") (pintype "passive"))
    )
    (net (code "39") (name "VCC_PV") (class "Default")
      (node (ref "R7") (pin "1") (pinfunction "1_1") (pintype "passive"))
      (node (ref "VPV") (pin "1") (pinfunction "1_1") (pintype "bidirectional"))
    )
    (net (code "40") (name "unconnected-(IC1-NC-Pad4)") (class "Default")
      (node (ref "IC1") (pin "4") (pinfunction "NC_4") (pintype "no_connect"))
    )
    (net (code "41") (name "unconnected-(IC5-ALERT{slash}RDY-Pad2)") (class "Default")
      (node (ref "IC5") (pin "2") (pinfunction "ALERT/RDY_2") (pintype "bidirectional"))
    )
    (net (code "42") (name "unconnected-(IC8-NC_1-Pad1)") (class "Default")
      (node (ref "IC8") (pin "1") (pinfunction "NC_1_1") (pintype "bidirectional"))
    )
    (net (code "43") (name "unconnected-(IC8-NC_2-Pad5)") (class "Default")
      (node (ref "IC8") (pin "5") (pinfunction "NC_2_5") (pintype "bidirectional"))
    )
    (net (code "44") (name "unconnected-(U$1-Pad2)") (class "Default")
      (node (ref "U$1") (pin "2") (pinfunction "2_2") (pintype "bidirectional"))
    )
    (net (code "45") (name "unconnected-(U$1-Pad13)") (class "Default")
      (node (ref "U$1") (pin "13") (pinfunction "13_13") (pintype "bidirectional"))
    )
    (net (code "46") (name "unconnected-(U$1-PadLORA1)") (class "Default")
      (node (ref "U$1") (pin "LORA1") (pinfunction "LORA1_LORA1") (pintype "bidirectional"))
    )
    (net (code "47") (name "unconnected-(U$1-PadLORA2)") (class "Default")
      (node (ref "U$1") (pin "LORA2") (pinfunction "LORA2_LORA2") (pintype "bidirectional"))
    )
    (net (code "48") (name "~{RXEN}") (class "Default")
      (node (ref "IC7") (pin "2") (pinfunction "~{RE}_2") (pintype "bidirectional"))
      (node (ref "R12") (pin "1") (pinfunction "1_1") (pintype "passive"))
      (node (ref "U$1") (pin "23") (pinfunction "23_23") (pintype "bidirectional"))
    )
  )
)
